# rotary_jack.net
KiCad netlist of a schematic drawn in EAGLE
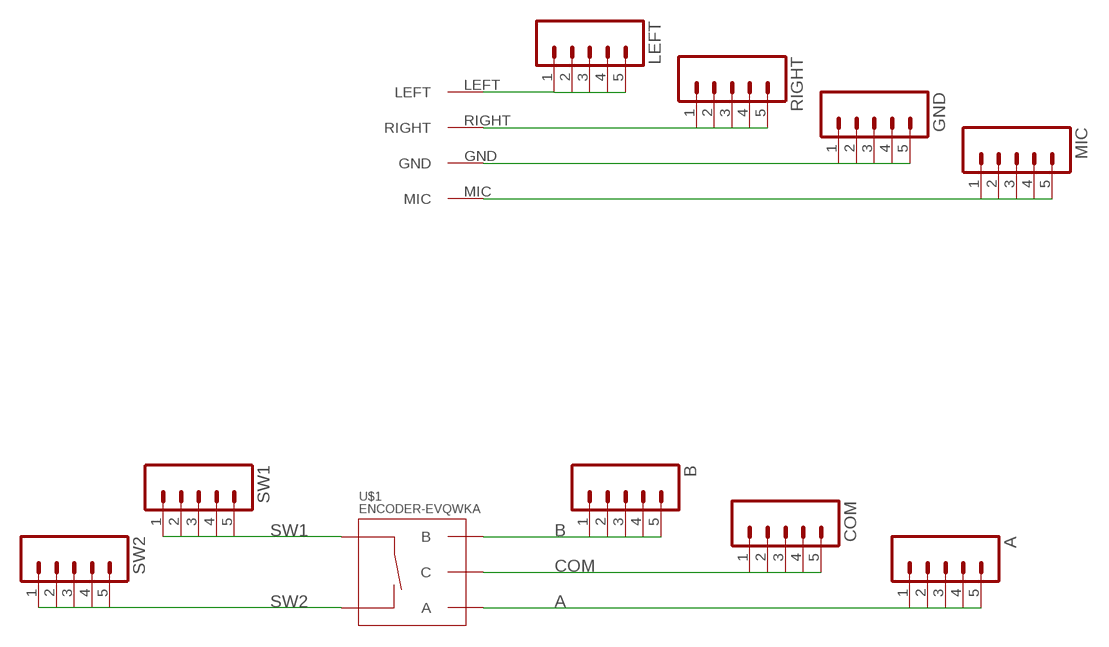
[diagram p0: schematic, sheet 1]

(export (version "E")
  (design (tool "Eeschema 10.0.6"))
  (components
    (comp (ref "A")
      (value "M05NO_SILK")
      (footprint "eagle-import:1X05_NO_SILK")
      (libsource (lib "eagle-import") (part "M05NO_SILK"))
    )
    (comp (ref "B")
      (value "M05NO_SILK")
      (footprint "eagle-import:1X05_NO_SILK")
      (libsource (lib "eagle-import") (part "M05NO_SILK"))
    )
    (comp (ref "COM")
      (value "M05NO_SILK")
      (footprint "eagle-import:1X05_NO_SILK")
      (libsource (lib "eagle-import") (part "M05NO_SILK"))
    )
    (comp (ref "GND")
      (value "M05NO_SILK")
      (footprint "eagle-import:1X05_NO_SILK")
      (libsource (lib "eagle-import") (part "M05NO_SILK"))
    )
    (comp (ref "LEFT")
      (value "M05NO_SILK")
      (footprint "eagle-import:1X05_NO_SILK")
      (libsource (lib "eagle-import") (part "M05NO_SILK"))
    )
    (comp (ref "MIC")
      (value "M05NO_SILK")
      (footprint "eagle-import:1X05_NO_SILK")
      (libsource (lib "eagle-import") (part "M05NO_SILK"))
    )
    (comp (ref "RIGHT")
      (value "M05NO_SILK")
      (footprint "eagle-import:1X05_NO_SILK")
      (libsource (lib "eagle-import") (part "M05NO_SILK"))
    )
    (comp (ref "SW1")
      (value "M05NO_SILK")
      (footprint "eagle-import:1X05_NO_SILK")
      (libsource (lib "eagle-import") (part "M05NO_SILK"))
    )
    (comp (ref "SW2")
      (value "M05NO_SILK")
      (footprint "eagle-import:1X05_NO_SILK")
      (libsource (lib "eagle-import") (part "M05NO_SILK"))
    )
    (comp (ref "U$1")
      (value "ENCODER-EVQWKA")
      (footprint "eagle-import:ENCODER-EVQWKA")
      (libsource (lib "eagle-import") (part "ENCODER-EVQWKA"))
    )
    (comp (ref "U$2")
      (value "MALE-HEADPHONEMIC")
      (footprint "eagle-import:MALEHEADPHONE")
      (libsource (lib "eagle-import") (part "MALE-HEADPHONEMIC"))
    )
  )
  (nets
    (net (code "1") (name "/A") (class "Default")
      (node (ref "A") (pin "1") (pinfunction "1_1") (pintype "passive"))
      (node (ref "A") (pin "2") (pinfunction "2_2") (pintype "passive"))
      (node (ref "A") (pin "3") (pinfunction "3_3") (pintype "passive"))
      (node (ref "A") (pin "4") (pinfunction "4_4") (pintype "passive"))
      (node (ref "A") (pin "5") (pinfunction "5_5") (pintype "passive"))
      (node (ref "U$1") (pin "A") (pinfunction "A_A") (pintype "bidirectional"))
    )
    (net (code "2") (name "/B") (class "Default")
      (node (ref "B") (pin "1") (pinfunction "1_1") (pintype "passive"))
      (node (ref "B") (pin "2") (pinfunction "2_2") (pintype "passive"))
      (node (ref "B") (pin "3") (pinfunction "3_3") (pintype "passive"))
      (node (ref "B") (pin "4") (pinfunction "4_4") (pintype "passive"))
      (node (ref "B") (pin "5") (pinfunction "5_5") (pintype "passive"))
      (node (ref "U$1") (pin "B") (pinfunction "B_B") (pintype "bidirectional"))
    )
    (net (code "3") (name "/COM") (class "Default")
      (node (ref "COM") (pin "1") (pinfunction "1_1") (pintype "passive"))
      (node (ref "COM") (pin "2") (pinfunction "2_2") (pintype "passive"))
      (node (ref "COM") (pin "3") (pinfunction "3_3") (pintype "passive"))
      (node (ref "COM") (pin "4") (pinfunction "4_4") (pintype "passive"))
      (node (ref "COM") (pin "5") (pinfunction "5_5") (pintype "passive"))
      (node (ref "U$1") (pin "COM") (pinfunction "C_COM") (pintype "bidirectional"))
    )
    (net (code "4") (name "/SW1") (class "Default")
      (node (ref "SW1") (pin "1") (pinfunction "1_1") (pintype "passive"))
      (node (ref "SW1") (pin "2") (pinfunction "2_2") (pintype "passive"))
      (node (ref "SW1") (pin "3") (pinfunction "3_3") (pintype "passive"))
      (node (ref "SW1") (pin "4") (pinfunction "4_4") (pintype "passive"))
      (node (ref "SW1") (pin "5") (pinfunction "5_5") (pintype "passive"))
      (node (ref "U$1") (pin "SW1") (pinfunction "SW+_SW1") (pintype "bidirectional"))
    )
    (net (code "5") (name "/SW2") (class "Default")
      (node (ref "SW2") (pin "1") (pinfunction "1_1") (pintype "passive"))
      (node (ref "SW2") (pin "2") (pinfunction "2_2") (pintype "passive"))
      (node (ref "SW2") (pin "3") (pinfunction "3_3") (pintype "passive"))
      (node (ref "SW2") (pin "4") (pinfunction "4_4") (pintype "passive"))
      (node (ref "SW2") (pin "5") (pinfunction "5_5") (pintype "passive"))
      (node (ref "U$1") (pin "SW2") (pinfunction "SW-_SW2") (pintype "bidirectional"))
    )
    (net (code "6") (name "Net-(GND-Pad1)") (class "Default")
      (node (ref "GND") (pin "1") (pinfunction "1_1") (pintype "passive"))
      (node (ref "GND") (pin "2") (pinfunction "2_2") (pintype "passive"))
      (node (ref "GND") (pin "3") (pinfunction "3_3") (pintype "passive"))
      (node (ref "GND") (pin "4") (pinfunction "4_4") (pintype "passive"))
      (node (ref "GND") (pin "5") (pinfunction "5_5") (pintype "passive"))
      (node (ref "U$2") (pin "GND") (pinfunction "GND_GND") (pintype "bidirectional"))
    )
    (net (code "7") (name "Net-(LEFT-Pad1)") (class "Default")
      (node (ref "LEFT") (pin "1") (pinfunction "1_1") (pintype "passive"))
      (node (ref "LEFT") (pin "2") (pinfunction "2_2") (pintype "passive"))
      (node (ref "LEFT") (pin "3") (pinfunction "3_3") (pintype "passive"))
      (node (ref "LEFT") (pin "4") (pinfunction "4_4") (pintype "passive"))
      (node (ref "LEFT") (pin "5") (pinfunction "5_5") (pintype "passive"))
      (node (ref "U$2") (pin "LEFT") (pinfunction "LEFT_LEFT") (pintype "bidirectional"))
    )
    (net (code "8") (name "Net-(MIC-Pad1)") (class "Default")
      (node (ref "MIC") (pin "1") (pinfunction "1_1") (pintype "passive"))
      (node (ref "MIC") (pin "2") (pinfunction "2_2") (pintype "passive"))
      (node (ref "MIC") (pin "3") (pinfunction "3_3") (pintype "passive"))
      (node (ref "MIC") (pin "4") (pinfunction "4_4") (pintype "passive"))
      (node (ref "MIC") (pin "5") (pinfunction "5_5") (pintype "passive"))
      (node (ref "U$2") (pin "MIC") (pinfunction "MIC_MIC") (pintype "bidirectional"))
    )
    (net (code "9") (name "Net-(RIGHT-Pad1)") (class "Default")
      (node (ref "RIGHT") (pin "1") (pinfunction "1_1") (pintype "passive"))
      (node (ref "RIGHT") (pin "2") (pinfunction "2_2") (pintype "passive"))
      (node (ref "RIGHT") (pin "3") (pinfunction "3_3") (pintype "passive"))
      (node (ref "RIGHT") (pin "4") (pinfunction "4_4") (pintype "passive"))
      (node (ref "RIGHT") (pin "5") (pinfunction "5_5") (pintype "passive"))
      (node (ref "U$2") (pin "RIGHT") (pinfunction "RIGHT_RIGHT") (pintype "bidirectional"))
    )
  )
)
